# CTR-Lower-Main-Board-Rev-C-LED.net
KiCad netlist of a schematic drawn in Altium Designer
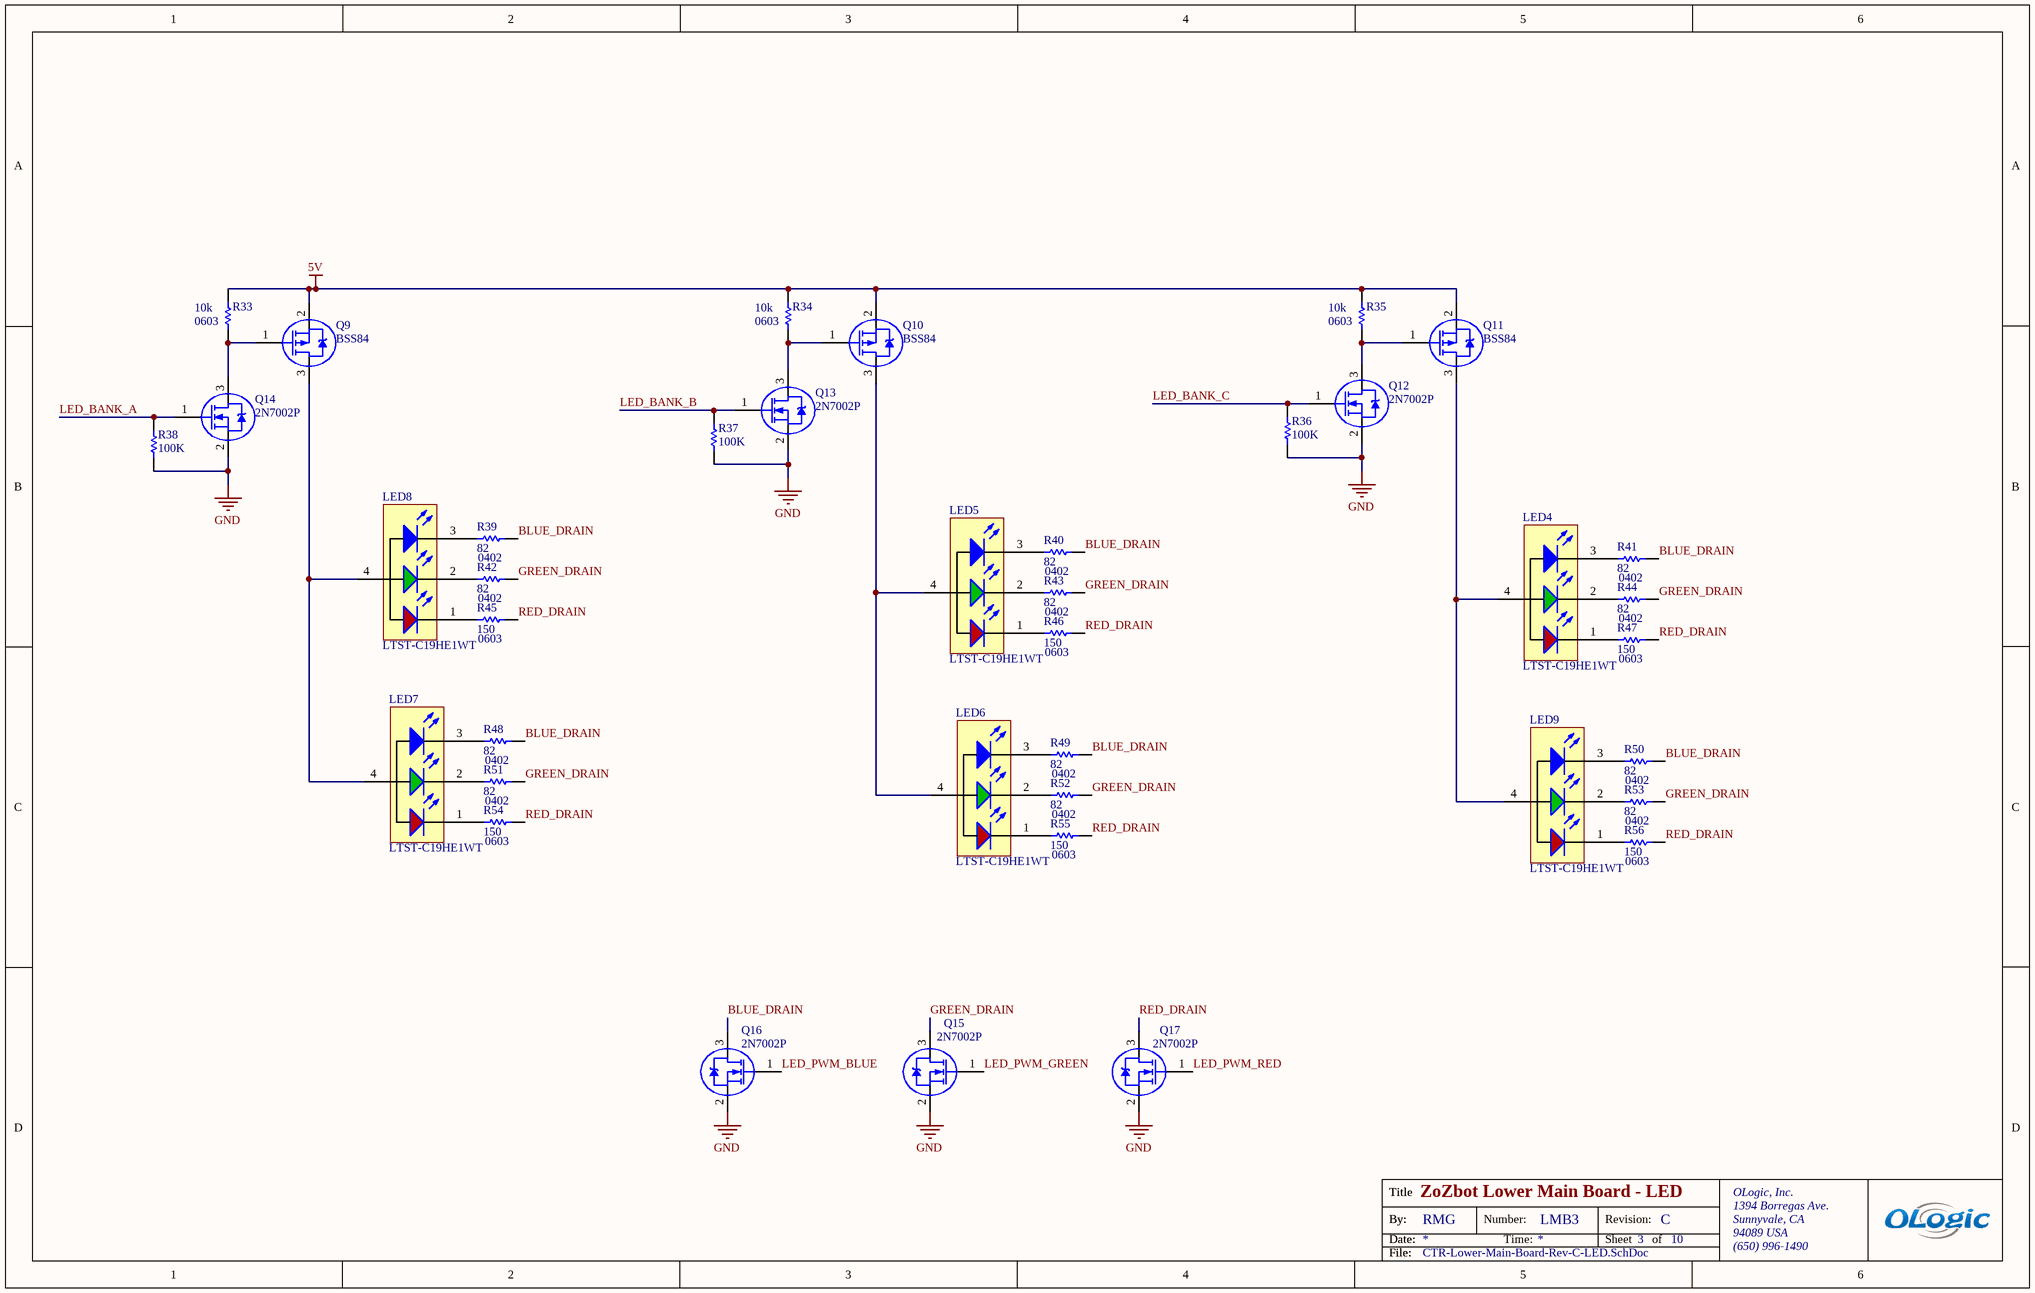
[diagram p0: CTR-Lower-Main-Board-Rev-C-LED.SchDoc]

(export (version "E")
  (design (tool "Eeschema 10.0.6"))
  (components
    (comp (ref "LED4")
      (value "Red, Green, Blue (RGB)")
      (footprint "LTST-C19HE1WT")
      (description "LED RGB 624/525/470NM DIFF SMD")
      (fields
        (field (name "MANUFACTURER") "Lite-On Inc.")
        (field (name "MANUFACTURER PART NUMBER") "LTST-C19HE1WT")
      )
      (libsource (lib "OLogic-Diode-Opto-LED") (part "LTST-C19HE1WT"))
    )
    (comp (ref "LED5")
      (value "Red, Green, Blue (RGB)")
      (footprint "LTST-C19HE1WT")
      (description "LED RGB 624/525/470NM DIFF SMD")
      (fields
        (field (name "MANUFACTURER") "Lite-On Inc.")
        (field (name "MANUFACTURER PART NUMBER") "LTST-C19HE1WT")
      )
      (libsource (lib "OLogic-Diode-Opto-LED") (part "LTST-C19HE1WT"))
    )
    (comp (ref "LED6")
      (value "Red, Green, Blue (RGB)")
      (footprint "LTST-C19HE1WT")
      (description "LED RGB 624/525/470NM DIFF SMD")
      (fields
        (field (name "MANUFACTURER") "Lite-On Inc.")
        (field (name "MANUFACTURER PART NUMBER") "LTST-C19HE1WT")
      )
      (libsource (lib "OLogic-Diode-Opto-LED") (part "LTST-C19HE1WT"))
    )
    (comp (ref "LED7")
      (value "Red, Green, Blue (RGB)")
      (footprint "LTST-C19HE1WT")
      (description "LED RGB 624/525/470NM DIFF SMD")
      (fields
        (field (name "MANUFACTURER") "Lite-On Inc.")
        (field (name "MANUFACTURER PART NUMBER") "LTST-C19HE1WT")
      )
      (libsource (lib "OLogic-Diode-Opto-LED") (part "LTST-C19HE1WT"))
    )
    (comp (ref "LED8")
      (value "Red, Green, Blue (RGB)")
      (footprint "LTST-C19HE1WT")
      (description "LED RGB 624/525/470NM DIFF SMD")
      (fields
        (field (name "MANUFACTURER") "Lite-On Inc.")
        (field (name "MANUFACTURER PART NUMBER") "LTST-C19HE1WT")
      )
      (libsource (lib "OLogic-Diode-Opto-LED") (part "LTST-C19HE1WT"))
    )
    (comp (ref "LED9")
      (value "Red, Green, Blue (RGB)")
      (footprint "LTST-C19HE1WT")
      (description "LED RGB 624/525/470NM DIFF SMD")
      (fields
        (field (name "MANUFACTURER") "Lite-On Inc.")
        (field (name "MANUFACTURER PART NUMBER") "LTST-C19HE1WT")
      )
      (libsource (lib "OLogic-Diode-Opto-LED") (part "LTST-C19HE1WT"))
    )
    (comp (ref "Q9")
      (value "BSS84")
      (footprint "SOT23")
      (description "MOSFET P-CH 50V 130MA SOT-23")
      (fields (field (name "MANUFACTURER") "Fairchild Semiconductor"))
      (libsource (lib "OLogic-Trans-Drivers") (part "BSS84"))
    )
    (comp (ref "Q10")
      (value "BSS84")
      (footprint "SOT23")
      (description "MOSFET P-CH 50V 130MA SOT-23")
      (fields (field (name "MANUFACTURER") "Fairchild Semiconductor"))
      (libsource (lib "OLogic-Trans-Drivers") (part "BSS84"))
    )
    (comp (ref "Q11")
      (value "BSS84")
      (footprint "SOT23")
      (description "MOSFET P-CH 50V 130MA SOT-23")
      (fields (field (name "MANUFACTURER") "Fairchild Semiconductor"))
      (libsource (lib "OLogic-Trans-Drivers") (part "BSS84"))
    )
    (comp (ref "Q12")
      (value "2N7002P")
      (footprint "SOT23")
      (description "MOSFET N-CH 60V 0.36A SOT-23")
      (fields
        (field (name "MANUFACTURER") "Nexperia USA Inc.")
        (field (name "MANUFACTURER PART NUMBER") "2N7002P,235")
      )
      (libsource (lib "") (part "2N7002P_1"))
    )
    (comp (ref "Q13")
      (value "2N7002P")
      (footprint "SOT23")
      (description "MOSFET N-CH 60V 0.36A SOT-23")
      (fields
        (field (name "MANUFACTURER") "Nexperia USA Inc.")
        (field (name "MANUFACTURER PART NUMBER") "2N7002P,235")
      )
      (libsource (lib "") (part "2N7002P_1"))
    )
    (comp (ref "Q14")
      (value "2N7002P")
      (footprint "SOT23")
      (description "MOSFET N-CH 60V 0.36A SOT-23")
      (fields
        (field (name "MANUFACTURER") "Nexperia USA Inc.")
        (field (name "MANUFACTURER PART NUMBER") "2N7002P,235")
      )
      (libsource (lib "") (part "2N7002P_1"))
    )
    (comp (ref "Q15")
      (value "2N7002P")
      (footprint "SOT23")
      (description "MOSFET N-CH 60V 0.36A SOT-23")
      (fields
        (field (name "MANUFACTURER") "Nexperia USA Inc.")
        (field (name "MANUFACTURER PART NUMBER") "2N7002P,235")
      )
      (libsource (lib "OLogic-Trans-Drivers") (part "2N7002P"))
    )
    (comp (ref "Q16")
      (value "2N7002P")
      (footprint "SOT23")
      (description "MOSFET N-CH 60V 0.36A SOT-23")
      (fields
        (field (name "MANUFACTURER") "Nexperia USA Inc.")
        (field (name "MANUFACTURER PART NUMBER") "2N7002P,235")
      )
      (libsource (lib "OLogic-Trans-Drivers") (part "2N7002P"))
    )
    (comp (ref "Q17")
      (value "2N7002P")
      (footprint "SOT23")
      (description "MOSFET N-CH 60V 0.36A SOT-23")
      (fields
        (field (name "MANUFACTURER") "Nexperia USA Inc.")
        (field (name "MANUFACTURER PART NUMBER") "2N7002P,235")
      )
      (libsource (lib "OLogic-Trans-Drivers") (part "2N7002P"))
    )
    (comp (ref "R33")
      (value "10K 1%")
      (footprint "RESC0603(1608)_N")
      (description "10K 0603")
      (fields
        (field (name "MANUFACTURER") "Panasonic Electronic Components")
        (field (name "MANUFACTURER PART NUMBER") "ERJ-3EKF1002V")
        (field (name "RESISTANCE (OHMS)") "10k")
        (field (name "SUPPLIER DEVICE PACKAGE") "0603")
      )
      (libsource (lib "OLogic-Passive") (part "RES 10K OHM 1/10W 1% 0603 SMD"))
    )
    (comp (ref "R34")
      (value "10K 1%")
      (footprint "RESC0603(1608)_N")
      (description "10K 0603")
      (fields
        (field (name "MANUFACTURER") "Panasonic Electronic Components")
        (field (name "MANUFACTURER PART NUMBER") "ERJ-3EKF1002V")
        (field (name "RESISTANCE (OHMS)") "10k")
        (field (name "SUPPLIER DEVICE PACKAGE") "0603")
      )
      (libsource (lib "OLogic-Passive") (part "RES 10K OHM 1/10W 1% 0603 SMD"))
    )
    (comp (ref "R35")
      (value "10K 1%")
      (footprint "RESC0603(1608)_N")
      (description "10K 0603")
      (fields
        (field (name "MANUFACTURER") "Panasonic Electronic Components")
        (field (name "MANUFACTURER PART NUMBER") "ERJ-3EKF1002V")
        (field (name "RESISTANCE (OHMS)") "10k")
        (field (name "SUPPLIER DEVICE PACKAGE") "0603")
      )
      (libsource (lib "OLogic-Passive") (part "RES 10K OHM 1/10W 1% 0603 SMD"))
    )
    (comp (ref "R36")
      (value "100K")
      (footprint "RESC0603(1608)_N")
      (description "100K 0603")
      (fields
        (field (name "MANUFACTURER") "Panasonic Electronic Components")
        (field (name "MANUFACTURER PART NUMBER") "ERJ-3GEYJ104V")
      )
      (libsource (lib "OLogic-Passive") (part "RES 100K OHM 1/10W 5% 0603 SMD"))
    )
    (comp (ref "R37")
      (value "100K")
      (footprint "RESC0603(1608)_N")
      (description "100K 0603")
      (fields
        (field (name "MANUFACTURER") "Panasonic Electronic Components")
        (field (name "MANUFACTURER PART NUMBER") "ERJ-3GEYJ104V")
      )
      (libsource (lib "OLogic-Passive") (part "RES 100K OHM 1/10W 5% 0603 SMD"))
    )
    (comp (ref "R38")
      (value "100K")
      (footprint "RESC0603(1608)_N")
      (description "100K 0603")
      (fields
        (field (name "MANUFACTURER") "Panasonic Electronic Components")
        (field (name "MANUFACTURER PART NUMBER") "ERJ-3GEYJ104V")
      )
      (libsource (lib "OLogic-Passive") (part "RES 100K OHM 1/10W 5% 0603 SMD"))
    )
    (comp (ref "R39")
      (value "?")
      (footprint "RESC0402(1005)_N")
      (description "82 0402")
      (fields
        (field (name "MANUFACTURER") "Panasonic Electronic Components")
        (field (name "MANUFACTURER PART NUMBER") "ERJ-2RKF82R0X")
        (field (name "SUPPLIER DEVICE PACKAGE") "0402")
        (field (name "RESISTANCE (OHMS)") "82")
        (field (name "CREATOR") "osman")
      )
      (libsource (lib "OLogic-Passive") (part "RES 82 OHM 1% 1/10W 0402"))
    )
    (comp (ref "R40")
      (value "?")
      (footprint "RESC0402(1005)_N")
      (description "82 0402")
      (fields
        (field (name "MANUFACTURER") "Panasonic Electronic Components")
        (field (name "MANUFACTURER PART NUMBER") "ERJ-2RKF82R0X")
        (field (name "SUPPLIER DEVICE PACKAGE") "0402")
        (field (name "RESISTANCE (OHMS)") "82")
        (field (name "CREATOR") "osman")
      )
      (libsource (lib "OLogic-Passive") (part "RES 82 OHM 1% 1/10W 0402"))
    )
    (comp (ref "R41")
      (value "?")
      (footprint "RESC0402(1005)_N")
      (description "82 0402")
      (fields
        (field (name "MANUFACTURER") "Panasonic Electronic Components")
        (field (name "MANUFACTURER PART NUMBER") "ERJ-2RKF82R0X")
        (field (name "SUPPLIER DEVICE PACKAGE") "0402")
        (field (name "RESISTANCE (OHMS)") "82")
        (field (name "CREATOR") "osman")
      )
      (libsource (lib "OLogic-Passive") (part "RES 82 OHM 1% 1/10W 0402"))
    )
    (comp (ref "R42")
      (value "?")
      (footprint "RESC0402(1005)_N")
      (description "82 0402")
      (fields
        (field (name "MANUFACTURER") "Panasonic Electronic Components")
        (field (name "MANUFACTURER PART NUMBER") "ERJ-2RKF82R0X")
        (field (name "SUPPLIER DEVICE PACKAGE") "0402")
        (field (name "RESISTANCE (OHMS)") "82")
        (field (name "CREATOR") "osman")
      )
      (libsource (lib "OLogic-Passive") (part "RES 82 OHM 1% 1/10W 0402"))
    )
    (comp (ref "R43")
      (value "?")
      (footprint "RESC0402(1005)_N")
      (description "82 0402")
      (fields
        (field (name "MANUFACTURER") "Panasonic Electronic Components")
        (field (name "MANUFACTURER PART NUMBER") "ERJ-2RKF82R0X")
        (field (name "SUPPLIER DEVICE PACKAGE") "0402")
        (field (name "RESISTANCE (OHMS)") "82")
        (field (name "CREATOR") "osman")
      )
      (libsource (lib "OLogic-Passive") (part "RES 82 OHM 1% 1/10W 0402"))
    )
    (comp (ref "R44")
      (value "?")
      (footprint "RESC0402(1005)_N")
      (description "82 0402")
      (fields
        (field (name "MANUFACTURER") "Panasonic Electronic Components")
        (field (name "MANUFACTURER PART NUMBER") "ERJ-2RKF82R0X")
        (field (name "SUPPLIER DEVICE PACKAGE") "0402")
        (field (name "RESISTANCE (OHMS)") "82")
        (field (name "CREATOR") "osman")
      )
      (libsource (lib "OLogic-Passive") (part "RES 82 OHM 1% 1/10W 0402"))
    )
    (comp (ref "R45")
      (value "150")
      (footprint "RESC0603(1608)_N")
      (description "150 0603")
      (fields
        (field (name "MANUFACTURER") "Yageo")
        (field (name "MANUFACTURER PART NUMBER") "RC0603FR-07150RL")
        (field (name "SUPPLIER DEVICE PACKAGE") "0603")
      )
      (libsource (lib "OLogic-Passive") (part "RES 150 OHM 1/10W 1% 0603 SMD"))
    )
    (comp (ref "R46")
      (value "150")
      (footprint "RESC0603(1608)_N")
      (description "150 0603")
      (fields
        (field (name "MANUFACTURER") "Yageo")
        (field (name "MANUFACTURER PART NUMBER") "RC0603FR-07150RL")
        (field (name "SUPPLIER DEVICE PACKAGE") "0603")
      )
      (libsource (lib "OLogic-Passive") (part "RES 150 OHM 1/10W 1% 0603 SMD"))
    )
    (comp (ref "R47")
      (value "150")
      (footprint "RESC0603(1608)_N")
      (description "150 0603")
      (fields
        (field (name "MANUFACTURER") "Yageo")
        (field (name "MANUFACTURER PART NUMBER") "RC0603FR-07150RL")
        (field (name "SUPPLIER DEVICE PACKAGE") "0603")
      )
      (libsource (lib "OLogic-Passive") (part "RES 150 OHM 1/10W 1% 0603 SMD"))
    )
    (comp (ref "R48")
      (value "?")
      (footprint "RESC0402(1005)_N")
      (description "82 0402")
      (fields
        (field (name "MANUFACTURER") "Panasonic Electronic Components")
        (field (name "MANUFACTURER PART NUMBER") "ERJ-2RKF82R0X")
        (field (name "SUPPLIER DEVICE PACKAGE") "0402")
        (field (name "RESISTANCE (OHMS)") "82")
        (field (name "CREATOR") "osman")
      )
      (libsource (lib "OLogic-Passive") (part "RES 82 OHM 1% 1/10W 0402"))
    )
    (comp (ref "R49")
      (value "?")
      (footprint "RESC0402(1005)_N")
      (description "82 0402")
      (fields
        (field (name "MANUFACTURER") "Panasonic Electronic Components")
        (field (name "MANUFACTURER PART NUMBER") "ERJ-2RKF82R0X")
        (field (name "SUPPLIER DEVICE PACKAGE") "0402")
        (field (name "RESISTANCE (OHMS)") "82")
        (field (name "CREATOR") "osman")
      )
      (libsource (lib "OLogic-Passive") (part "RES 82 OHM 1% 1/10W 0402"))
    )
    (comp (ref "R50")
      (value "?")
      (footprint "RESC0402(1005)_N")
      (description "82 0402")
      (fields
        (field (name "MANUFACTURER") "Panasonic Electronic Components")
        (field (name "MANUFACTURER PART NUMBER") "ERJ-2RKF82R0X")
        (field (name "SUPPLIER DEVICE PACKAGE") "0402")
        (field (name "RESISTANCE (OHMS)") "82")
        (field (name "CREATOR") "osman")
      )
      (libsource (lib "OLogic-Passive") (part "RES 82 OHM 1% 1/10W 0402"))
    )
    (comp (ref "R51")
      (value "?")
      (footprint "RESC0402(1005)_N")
      (description "82 0402")
      (fields
        (field (name "MANUFACTURER") "Panasonic Electronic Components")
        (field (name "MANUFACTURER PART NUMBER") "ERJ-2RKF82R0X")
        (field (name "SUPPLIER DEVICE PACKAGE") "0402")
        (field (name "RESISTANCE (OHMS)") "82")
        (field (name "CREATOR") "osman")
      )
      (libsource (lib "OLogic-Passive") (part "RES 82 OHM 1% 1/10W 0402"))
    )
    (comp (ref "R52")
      (value "?")
      (footprint "RESC0402(1005)_N")
      (description "82 0402")
      (fields
        (field (name "MANUFACTURER") "Panasonic Electronic Components")
        (field (name "MANUFACTURER PART NUMBER") "ERJ-2RKF82R0X")
        (field (name "SUPPLIER DEVICE PACKAGE") "0402")
        (field (name "RESISTANCE (OHMS)") "82")
        (field (name "CREATOR") "osman")
      )
      (libsource (lib "OLogic-Passive") (part "RES 82 OHM 1% 1/10W 0402"))
    )
    (comp (ref "R53")
      (value "?")
      (footprint "RESC0402(1005)_N")
      (description "82 0402")
      (fields
        (field (name "MANUFACTURER") "Panasonic Electronic Components")
        (field (name "MANUFACTURER PART NUMBER") "ERJ-2RKF82R0X")
        (field (name "SUPPLIER DEVICE PACKAGE") "0402")
        (field (name "RESISTANCE (OHMS)") "82")
        (field (name "CREATOR") "osman")
      )
      (libsource (lib "OLogic-Passive") (part "RES 82 OHM 1% 1/10W 0402"))
    )
    (comp (ref "R54")
      (value "150")
      (footprint "RESC0603(1608)_N")
      (description "150 0603")
      (fields
        (field (name "MANUFACTURER") "Yageo")
        (field (name "MANUFACTURER PART NUMBER") "RC0603FR-07150RL")
        (field (name "SUPPLIER DEVICE PACKAGE") "0603")
      )
      (libsource (lib "OLogic-Passive") (part "RES 150 OHM 1/10W 1% 0603 SMD"))
    )
    (comp (ref "R55")
      (value "150")
      (footprint "RESC0603(1608)_N")
      (description "150 0603")
      (fields
        (field (name "MANUFACTURER") "Yageo")
        (field (name "MANUFACTURER PART NUMBER") "RC0603FR-07150RL")
        (field (name "SUPPLIER DEVICE PACKAGE") "0603")
      )
      (libsource (lib "OLogic-Passive") (part "RES 150 OHM 1/10W 1% 0603 SMD"))
    )
    (comp (ref "R56")
      (value "150")
      (footprint "RESC0603(1608)_N")
      (description "150 0603")
      (fields
        (field (name "MANUFACTURER") "Yageo")
        (field (name "MANUFACTURER PART NUMBER") "RC0603FR-07150RL")
        (field (name "SUPPLIER DEVICE PACKAGE") "0603")
      )
      (libsource (lib "OLogic-Passive") (part "RES 150 OHM 1/10W 1% 0603 SMD"))
    )
  )
  (nets
    (net (code "1") (name "/BLUE_DRAIN") (class "Default")
      (node (ref "Q16") (pin "3") (pinfunction "D_3") (pintype "passive"))
      (node (ref "R39") (pin "1") (pinfunction "1_1") (pintype "passive"))
      (node (ref "R40") (pin "1") (pinfunction "1_1") (pintype "passive"))
      (node (ref "R41") (pin "1") (pinfunction "1_1") (pintype "passive"))
      (node (ref "R48") (pin "1") (pinfunction "1_1") (pintype "passive"))
      (node (ref "R49") (pin "1") (pinfunction "1_1") (pintype "passive"))
      (node (ref "R50") (pin "1") (pinfunction "1_1") (pintype "passive"))
    )
    (net (code "2") (name "/GREEN_DRAIN") (class "Default")
      (node (ref "Q15") (pin "3") (pinfunction "D_3") (pintype "passive"))
      (node (ref "R42") (pin "1") (pinfunction "1_1") (pintype "passive"))
      (node (ref "R43") (pin "1") (pinfunction "1_1") (pintype "passive"))
      (node (ref "R44") (pin "1") (pinfunction "1_1") (pintype "passive"))
      (node (ref "R51") (pin "1") (pinfunction "1_1") (pintype "passive"))
      (node (ref "R52") (pin "1") (pinfunction "1_1") (pintype "passive"))
      (node (ref "R53") (pin "1") (pinfunction "1_1") (pintype "passive"))
    )
    (net (code "3") (name "/LED_BANK_A") (class "Default")
      (node (ref "Q14") (pin "1") (pinfunction "G_1") (pintype "passive"))
      (node (ref "R38") (pin "2") (pinfunction "2_2") (pintype "passive"))
    )
    (net (code "4") (name "/LED_BANK_B") (class "Default")
      (node (ref "Q13") (pin "1") (pinfunction "G_1") (pintype "passive"))
      (node (ref "R37") (pin "2") (pinfunction "2_2") (pintype "passive"))
    )
    (net (code "5") (name "/LED_BANK_C") (class "Default")
      (node (ref "Q12") (pin "1") (pinfunction "G_1") (pintype "passive"))
      (node (ref "R36") (pin "2") (pinfunction "2_2") (pintype "passive"))
    )
    (net (code "6") (name "/LED_PWM_BLUE") (class "Default")
      (node (ref "Q16") (pin "1") (pinfunction "G_1") (pintype "passive"))
    )
    (net (code "7") (name "/LED_PWM_GREEN") (class "Default")
      (node (ref "Q15") (pin "1") (pinfunction "G_1") (pintype "passive"))
    )
    (net (code "8") (name "/LED_PWM_RED") (class "Default")
      (node (ref "Q17") (pin "1") (pinfunction "G_1") (pintype "passive"))
    )
    (net (code "9") (name "/RED_DRAIN") (class "Default")
      (node (ref "Q17") (pin "3") (pinfunction "D_3") (pintype "passive"))
      (node (ref "R45") (pin "1") (pinfunction "1_1") (pintype "passive"))
      (node (ref "R46") (pin "1") (pinfunction "1_1") (pintype "passive"))
      (node (ref "R47") (pin "1") (pinfunction "1_1") (pintype "passive"))
      (node (ref "R54") (pin "1") (pinfunction "1_1") (pintype "passive"))
      (node (ref "R55") (pin "1") (pinfunction "1_1") (pintype "passive"))
      (node (ref "R56") (pin "1") (pinfunction "1_1") (pintype "passive"))
    )
    (net (code "10") (name "5V") (class "Default")
      (node (ref "Q10") (pin "2") (pinfunction "S_2") (pintype "passive"))
      (node (ref "Q11") (pin "2") (pinfunction "S_2") (pintype "passive"))
      (node (ref "Q9") (pin "2") (pinfunction "S_2") (pintype "passive"))
      (node (ref "R33") (pin "2") (pinfunction "2_2") (pintype "passive"))
      (node (ref "R34") (pin "2") (pinfunction "2_2") (pintype "passive"))
      (node (ref "R35") (pin "2") (pinfunction "2_2") (pintype "passive"))
    )
    (net (code "11") (name "GND") (class "Default")
      (node (ref "Q12") (pin "2") (pinfunction "S_2") (pintype "passive"))
      (node (ref "Q13") (pin "2") (pinfunction "S_2") (pintype "passive"))
      (node (ref "Q14") (pin "2") (pinfunction "S_2") (pintype "passive"))
      (node (ref "Q15") (pin "2") (pinfunction "S_2") (pintype "passive"))
      (node (ref "Q16") (pin "2") (pinfunction "S_2") (pintype "passive"))
      (node (ref "Q17") (pin "2") (pinfunction "S_2") (pintype "passive"))
      (node (ref "R36") (pin "1") (pinfunction "1_1") (pintype "passive"))
      (node (ref "R37") (pin "1") (pinfunction "1_1") (pintype "passive"))
      (node (ref "R38") (pin "1") (pinfunction "1_1") (pintype "passive"))
    )
    (net (code "12") (name "Net-(LED4-Anode)") (class "Default")
      (node (ref "LED4") (pin "4") (pinfunction "Anode_4") (pintype "passive"))
      (node (ref "LED9") (pin "4") (pinfunction "Anode_4") (pintype "passive"))
      (node (ref "Q11") (pin "3") (pinfunction "D_3") (pintype "passive"))
    )
    (net (code "13") (name "Net-(LED4-B)") (class "Default")
      (node (ref "LED4") (pin "3") (pinfunction "B_3") (pintype "passive"))
      (node (ref "R41") (pin "2") (pinfunction "2_2") (pintype "passive"))
    )
    (net (code "14") (name "Net-(LED4-G)") (class "Default")
      (node (ref "LED4") (pin "2") (pinfunction "G_2") (pintype "passive"))
      (node (ref "R44") (pin "2") (pinfunction "2_2") (pintype "passive"))
    )
    (net (code "15") (name "Net-(LED4-R)") (class "Default")
      (node (ref "LED4") (pin "1") (pinfunction "R_1") (pintype "passive"))
      (node (ref "R47") (pin "2") (pinfunction "2_2") (pintype "passive"))
    )
    (net (code "16") (name "Net-(LED5-Anode)") (class "Default")
      (node (ref "LED5") (pin "4") (pinfunction "Anode_4") (pintype "passive"))
      (node (ref "LED6") (pin "4") (pinfunction "Anode_4") (pintype "passive"))
      (node (ref "Q10") (pin "3") (pinfunction "D_3") (pintype "passive"))
    )
    (net (code "17") (name "Net-(LED5-B)") (class "Default")
      (node (ref "LED5") (pin "3") (pinfunction "B_3") (pintype "passive"))
      (node (ref "R40") (pin "2") (pinfunction "2_2") (pintype "passive"))
    )
    (net (code "18") (name "Net-(LED5-G)") (class "Default")
      (node (ref "LED5") (pin "2") (pinfunction "G_2") (pintype "passive"))
      (node (ref "R43") (pin "2") (pinfunction "2_2") (pintype "passive"))
    )
    (net (code "19") (name "Net-(LED5-R)") (class "Default")
      (node (ref "LED5") (pin "1") (pinfunction "R_1") (pintype "passive"))
      (node (ref "R46") (pin "2") (pinfunction "2_2") (pintype "passive"))
    )
    (net (code "20") (name "Net-(LED6-B)") (class "Default")
      (node (ref "LED6") (pin "3") (pinfunction "B_3") (pintype "passive"))
      (node (ref "R49") (pin "2") (pinfunction "2_2") (pintype "passive"))
    )
    (net (code "21") (name "Net-(LED6-G)") (class "Default")
      (node (ref "LED6") (pin "2") (pinfunction "G_2") (pintype "passive"))
      (node (ref "R52") (pin "2") (pinfunction "2_2") (pintype "passive"))
    )
    (net (code "22") (name "Net-(LED6-R)") (class "Default")
      (node (ref "LED6") (pin "1") (pinfunction "R_1") (pintype "passive"))
      (node (ref "R55") (pin "2") (pinfunction "2_2") (pintype "passive"))
    )
    (net (code "23") (name "Net-(LED7-Anode)") (class "Default")
      (node (ref "LED7") (pin "4") (pinfunction "Anode_4") (pintype "passive"))
      (node (ref "LED8") (pin "4") (pinfunction "Anode_4") (pintype "passive"))
      (node (ref "Q9") (pin "3") (pinfunction "D_3") (pintype "passive"))
    )
    (net (code "24") (name "Net-(LED7-B)") (class "Default")
      (node (ref "LED7") (pin "3") (pinfunction "B_3") (pintype "passive"))
      (node (ref "R48") (pin "2") (pinfunction "2_2") (pintype "passive"))
    )
    (net (code "25") (name "Net-(LED7-G)") (class "Default")
      (node (ref "LED7") (pin "2") (pinfunction "G_2") (pintype "passive"))
      (node (ref "R51") (pin "2") (pinfunction "2_2") (pintype "passive"))
    )
    (net (code "26") (name "Net-(LED7-R)") (class "Default")
      (node (ref "LED7") (pin "1") (pinfunction "R_1") (pintype "passive"))
      (node (ref "R54") (pin "2") (pinfunction "2_2") (pintype "passive"))
    )
    (net (code "27") (name "Net-(LED8-B)") (class "Default")
      (node (ref "LED8") (pin "3") (pinfunction "B_3") (pintype "passive"))
      (node (ref "R39") (pin "2") (pinfunction "2_2") (pintype "passive"))
    )
    (net (code "28") (name "Net-(LED8-G)") (class "Default")
      (node (ref "LED8") (pin "2") (pinfunction "G_2") (pintype "passive"))
      (node (ref "R42") (pin "2") (pinfunction "2_2") (pintype "passive"))
    )
    (net (code "29") (name "Net-(LED8-R)") (class "Default")
      (node (ref "LED8") (pin "1") (pinfunction "R_1") (pintype "passive"))
      (node (ref "R45") (pin "2") (pinfunction "2_2") (pintype "passive"))
    )
    (net (code "30") (name "Net-(LED9-B)") (class "Default")
      (node (ref "LED9") (pin "3") (pinfunction "B_3") (pintype "passive"))
      (node (ref "R50") (pin "2") (pinfunction "2_2") (pintype "passive"))
    )
    (net (code "31") (name "Net-(LED9-G)") (class "Default")
      (node (ref "LED9") (pin "2") (pinfunction "G_2") (pintype "passive"))
      (node (ref "R53") (pin "2") (pinfunction "2_2") (pintype "passive"))
    )
    (net (code "32") (name "Net-(LED9-R)") (class "Default")
      (node (ref "LED9") (pin "1") (pinfunction "R_1") (pintype "passive"))
      (node (ref "R56") (pin "2") (pinfunction "2_2") (pintype "passive"))
    )
    (net (code "33") (name "Net-(Q10-G)") (class "Default")
      (node (ref "Q10") (pin "1") (pinfunction "G_1") (pintype "passive"))
      (node (ref "Q13") (pin "3") (pinfunction "D_3") (pintype "passive"))
      (node (ref "R34") (pin "1") (pinfunction "1_1") (pintype "passive"))
    )
    (net (code "34") (name "Net-(Q11-G)") (class "Default")
      (node (ref "Q11") (pin "1") (pinfunction "G_1") (pintype "passive"))
      (node (ref "Q12") (pin "3") (pinfunction "D_3") (pintype "passive"))
      (node (ref "R35") (pin "1") (pinfunction "1_1") (pintype "passive"))
    )
    (net (code "35") (name "Net-(Q14-D)") (class "Default")
      (node (ref "Q14") (pin "3") (pinfunction "D_3") (pintype "passive"))
      (node (ref "Q9") (pin "1") (pinfunction "G_1") (pintype "passive"))
      (node (ref "R33") (pin "1") (pinfunction "1_1") (pintype "passive"))
    )
  )
)
